# shield.net
KiCad netlist of a schematic drawn in EAGLE
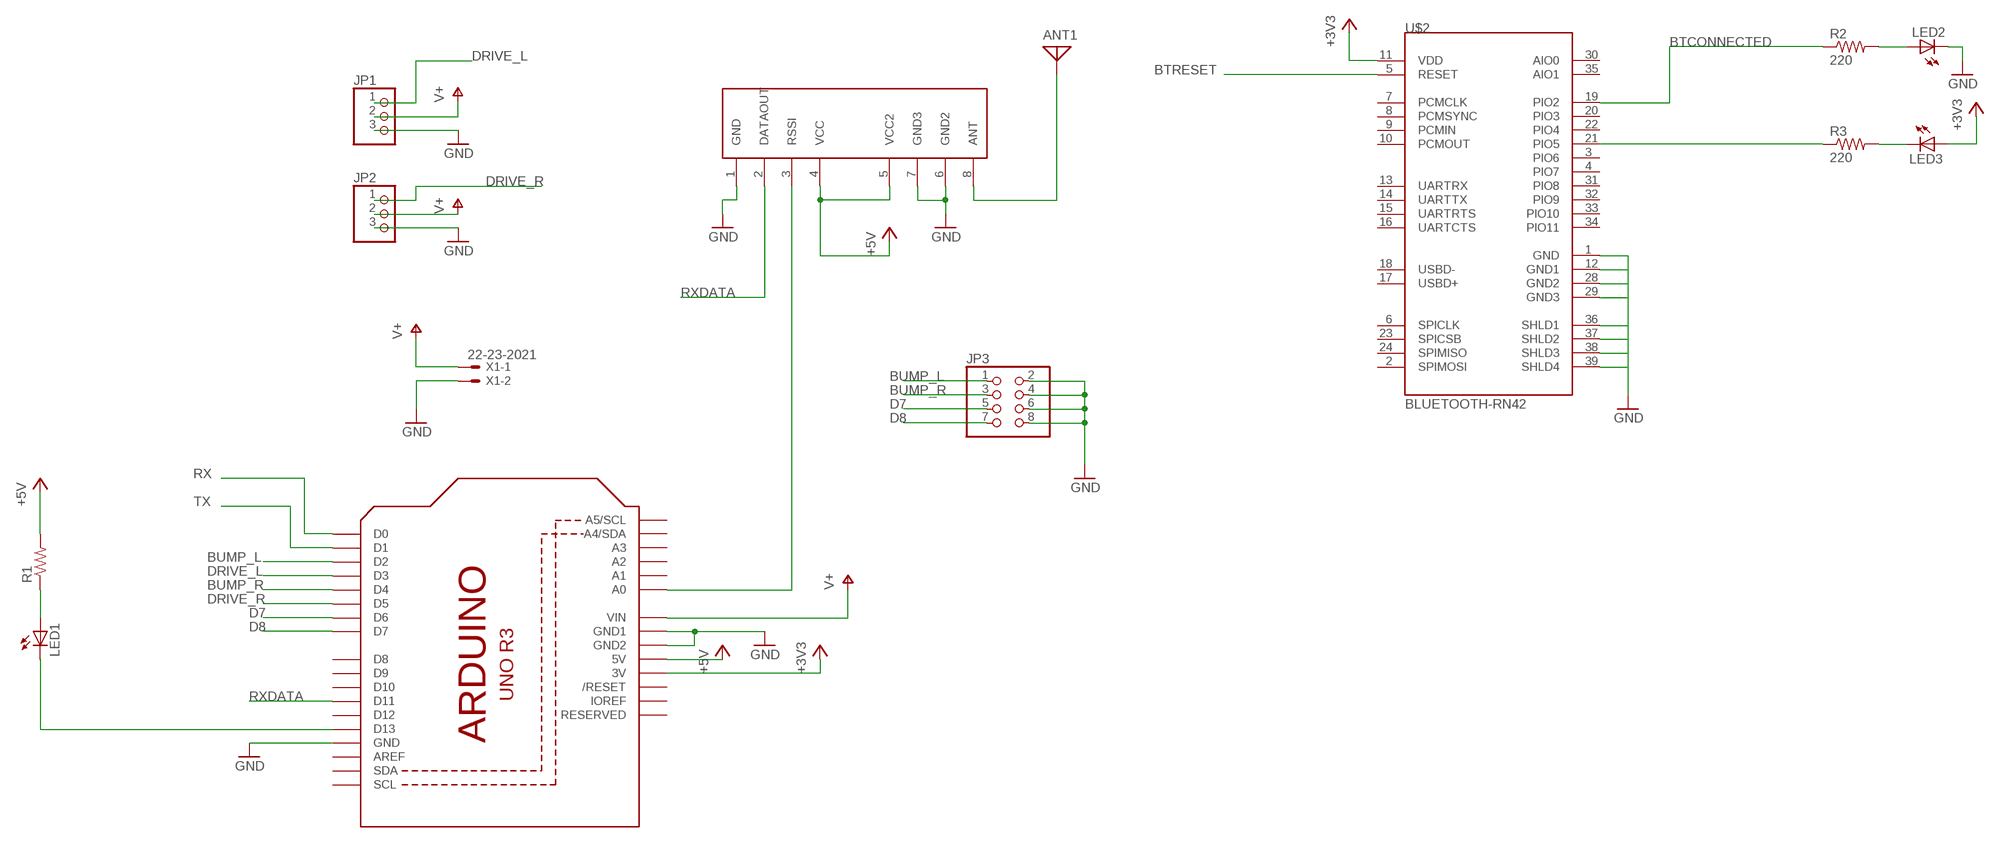
[diagram p0: schematic, sheet 1]

(export (version "E")
  (design (tool "Eeschema 10.0.6"))
  (components
    (comp (ref "ANT1")
      (value "ANTENNA")
      (footprint "eagle-import:PAD-01")
      (libsource (lib "eagle-import") (part "ANTENNA"))
    )
    (comp (ref "JP1")
      (value "PINHD-1X3")
      (footprint "eagle-import:1X03")
      (libsource (lib "eagle-import") (part "PINHD-1X3"))
    )
    (comp (ref "JP2")
      (value "PINHD-1X3")
      (footprint "eagle-import:1X03")
      (libsource (lib "eagle-import") (part "PINHD-1X3"))
    )
    (comp (ref "JP3")
      (value "PINHD-2X4")
      (footprint "eagle-import:2X04")
      (libsource (lib "eagle-import") (part "PINHD-2X4"))
    )
    (comp (ref "LED1")
      (value "LED3MM")
      (footprint "eagle-import:LED3MM")
      (libsource (lib "eagle-import") (part "LED3MM"))
    )
    (comp (ref "LED2")
      (value "LED3MM")
      (footprint "eagle-import:LED3MM")
      (libsource (lib "eagle-import") (part "LED3MM"))
    )
    (comp (ref "LED3")
      (value "LED3MM")
      (footprint "eagle-import:LED3MM")
      (libsource (lib "eagle-import") (part "LED3MM"))
    )
    (comp (ref "R1")
      (value "R-US_R0805")
      (footprint "eagle-import:R0805")
      (libsource (lib "eagle-import") (part "R-US_R0805"))
    )
    (comp (ref "R2")
      (value "220")
      (footprint "eagle-import:R0805")
      (libsource (lib "eagle-import") (part "R-US_R0805"))
    )
    (comp (ref "R3")
      (value "220")
      (footprint "eagle-import:R0805")
      (libsource (lib "eagle-import") (part "R-US_R0805"))
    )
    (comp (ref "U$1")
      (value "RWS371")
      (footprint "eagle-import:RWS-371")
      (libsource (lib "eagle-import") (part "RWS371"))
    )
    (comp (ref "U$2")
      (value "BLUETOOTH-RN42")
      (footprint "eagle-import:RN42")
      (libsource (lib "eagle-import") (part "BLUETOOTH-RN42"))
    )
    (comp (ref "U1")
      (value "ARDUINOR3-DIMENSION")
      (footprint "eagle-import:ARDUINOR3")
      (libsource (lib "eagle-import") (part "ARDUINOR3-DIMENSION"))
    )
    (comp (ref "X1")
      (value "22-23-2021")
      (footprint "eagle-import:22-23-2021")
      (fields (field (name "MF") "MOLEX"))
      (libsource (lib "eagle-import") (part "22-23-2021"))
    )
  )
  (nets
    (net (code "1") (name "+3V3") (class "Default")
      (node (ref "LED3") (pin "A") (pinfunction "A_A") (pintype "passive"))
      (node (ref "U$2") (pin "11") (pinfunction "VDD_11") (pintype "power_in"))
      (node (ref "U1") (pin "3V") (pinfunction "3V_3V") (pintype "power_in"))
    )
    (net (code "2") (name "+5V") (class "Default")
      (node (ref "R1") (pin "2") (pinfunction "2_2") (pintype "passive"))
      (node (ref "U$1") (pin "4") (pinfunction "VCC_4") (pintype "power_in"))
      (node (ref "U$1") (pin "5") (pinfunction "VCC2_5") (pintype "power_in"))
      (node (ref "U1") (pin "5V") (pinfunction "5V_5V") (pintype "power_in"))
    )
    (net (code "3") (name "/BTCONNECTED") (class "Default")
      (node (ref "R2") (pin "1") (pinfunction "1_1") (pintype "passive"))
      (node (ref "U$2") (pin "19") (pinfunction "PIO2_19") (pintype "bidirectional"))
    )
    (net (code "4") (name "/BTRESET") (class "Default")
      (node (ref "U$2") (pin "5") (pinfunction "RESET_5") (pintype "bidirectional"))
    )
    (net (code "5") (name "/BUMP_L") (class "Default")
      (node (ref "JP3") (pin "1") (pinfunction "1_1") (pintype "passive"))
      (node (ref "U1") (pin "D2") (pinfunction "D2_D2") (pintype "bidirectional"))
    )
    (net (code "6") (name "/BUMP_R") (class "Default")
      (node (ref "JP3") (pin "3") (pinfunction "3_3") (pintype "passive"))
      (node (ref "U1") (pin "D4") (pinfunction "D4_D4") (pintype "bidirectional"))
    )
    (net (code "7") (name "/D7") (class "Default")
      (node (ref "JP3") (pin "5") (pinfunction "5_5") (pintype "passive"))
      (node (ref "U1") (pin "D6") (pinfunction "D6_D6") (pintype "bidirectional"))
    )
    (net (code "8") (name "/D8") (class "Default")
      (node (ref "JP3") (pin "7") (pinfunction "7_7") (pintype "passive"))
      (node (ref "U1") (pin "D7") (pinfunction "D7_D7") (pintype "bidirectional"))
    )
    (net (code "9") (name "/DRIVE_L") (class "Default")
      (node (ref "JP1") (pin "1") (pinfunction "1_1") (pintype "passive"))
      (node (ref "U1") (pin "D3") (pinfunction "D3_D3") (pintype "bidirectional"))
    )
    (net (code "10") (name "/DRIVE_R") (class "Default")
      (node (ref "JP2") (pin "1") (pinfunction "1_1") (pintype "passive"))
      (node (ref "U1") (pin "D5") (pinfunction "D5_D5") (pintype "bidirectional"))
    )
    (net (code "11") (name "/RX") (class "Default")
      (node (ref "U1") (pin "D0") (pinfunction "D0_D0") (pintype "bidirectional"))
    )
    (net (code "12") (name "/RXDATA") (class "Default")
      (node (ref "U$1") (pin "2") (pinfunction "DATAOUT_2") (pintype "output"))
      (node (ref "U1") (pin "D11") (pinfunction "D11_D11") (pintype "bidirectional"))
    )
    (net (code "13") (name "/TX") (class "Default")
      (node (ref "U1") (pin "D1") (pinfunction "D1_D1") (pintype "bidirectional"))
    )
    (net (code "14") (name "GND") (class "Default")
      (node (ref "JP1") (pin "3") (pinfunction "3_3") (pintype "passive"))
      (node (ref "JP2") (pin "3") (pinfunction "3_3") (pintype "passive"))
      (node (ref "JP3") (pin "2") (pinfunction "2_2") (pintype "passive"))
      (node (ref "JP3") (pin "4") (pinfunction "4_4") (pintype "passive"))
      (node (ref "JP3") (pin "6") (pinfunction "6_6") (pintype "passive"))
      (node (ref "JP3") (pin "8") (pinfunction "8_8") (pintype "passive"))
      (node (ref "LED2") (pin "K") (pinfunction "C_K") (pintype "passive"))
      (node (ref "U$1") (pin "1") (pinfunction "GND_1") (pintype "power_in"))
      (node (ref "U$1") (pin "6") (pinfunction "GND2_6") (pintype "bidirectional"))
      (node (ref "U$1") (pin "7") (pinfunction "GND3_7") (pintype "bidirectional"))
      (node (ref "U$2") (pin "1") (pinfunction "GND_1") (pintype "power_in"))
      (node (ref "U$2") (pin "12") (pinfunction "GND1_12") (pintype "power_in"))
      (node (ref "U$2") (pin "28") (pinfunction "GND2_28") (pintype "power_in"))
      (node (ref "U$2") (pin "29") (pinfunction "GND3_29") (pintype "power_in"))
      (node (ref "U$2") (pin "36") (pinfunction "SHLD1_36") (pintype "power_in"))
      (node (ref "U$2") (pin "37") (pinfunction "SHLD2_37") (pintype "power_in"))
      (node (ref "U$2") (pin "38") (pinfunction "SHLD3_38") (pintype "power_in"))
      (node (ref "U$2") (pin "39") (pinfunction "SHLD4_39") (pintype "power_in"))
      (node (ref "U1") (pin "GND") (pinfunction "GND_GND") (pintype "power_in"))
      (node (ref "U1") (pin "GND1") (pinfunction "GND1_GND1") (pintype "power_in"))
      (node (ref "U1") (pin "GND2") (pinfunction "GND2_GND2") (pintype "power_in"))
      (node (ref "X1") (pin "2") (pinfunction "S_2") (pintype "passive"))
    )
    (net (code "15") (name "Net-(LED1-C)") (class "Default")
      (node (ref "LED1") (pin "K") (pinfunction "C_K") (pintype "passive"))
      (node (ref "U1") (pin "D13") (pinfunction "D13_D13") (pintype "bidirectional"))
    )
    (net (code "16") (name "Net-(LED1-PadA)") (class "Default")
      (node (ref "LED1") (pin "A") (pinfunction "A_A") (pintype "passive"))
      (node (ref "R1") (pin "1") (pinfunction "1_1") (pintype "passive"))
    )
    (net (code "17") (name "Net-(LED2-PadA)") (class "Default")
      (node (ref "LED2") (pin "A") (pinfunction "A_A") (pintype "passive"))
      (node (ref "R2") (pin "2") (pinfunction "2_2") (pintype "passive"))
    )
    (net (code "18") (name "Net-(LED3-C)") (class "Default")
      (node (ref "LED3") (pin "K") (pinfunction "C_K") (pintype "passive"))
      (node (ref "R3") (pin "2") (pinfunction "2_2") (pintype "passive"))
    )
    (net (code "19") (name "Net-(U$1-ANT)") (class "Default")
      (node (ref "ANT1") (pin "1") (pinfunction "1_1") (pintype "output"))
      (node (ref "U$1") (pin "8") (pinfunction "ANT_8") (pintype "bidirectional"))
    )
    (net (code "20") (name "Net-(U$1-RSSI)") (class "Default")
      (node (ref "U$1") (pin "3") (pinfunction "RSSI_3") (pintype "output"))
      (node (ref "U1") (pin "A0") (pinfunction "A0_A0") (pintype "bidirectional"))
    )
    (net (code "21") (name "Net-(U$2-PIO5)") (class "Default")
      (node (ref "R3") (pin "1") (pinfunction "1_1") (pintype "passive"))
      (node (ref "U$2") (pin "21") (pinfunction "PIO5_21") (pintype "bidirectional"))
    )
    (net (code "22") (name "V+") (class "Default")
      (node (ref "JP1") (pin "2") (pinfunction "2_2") (pintype "passive"))
      (node (ref "JP2") (pin "2") (pinfunction "2_2") (pintype "passive"))
      (node (ref "U1") (pin "VIN") (pinfunction "VIN_VIN") (pintype "power_in"))
      (node (ref "X1") (pin "1") (pinfunction "S_1") (pintype "passive"))
    )
    (net (code "23") (name "unconnected-(U$2-AIO0-Pad30)") (class "Default")
      (node (ref "U$2") (pin "30") (pinfunction "AIO0_30") (pintype "bidirectional"))
    )
    (net (code "24") (name "unconnected-(U$2-AIO1-Pad35)") (class "Default")
      (node (ref "U$2") (pin "35") (pinfunction "AIO1_35") (pintype "bidirectional"))
    )
    (net (code "25") (name "unconnected-(U$2-PCMCLK-Pad7)") (class "Default")
      (node (ref "U$2") (pin "7") (pinfunction "PCMCLK_7") (pintype "bidirectional"))
    )
    (net (code "26") (name "unconnected-(U$2-PCMIN-Pad9)") (class "Default")
      (node (ref "U$2") (pin "9") (pinfunction "PCMIN_9") (pintype "bidirectional"))
    )
    (net (code "27") (name "unconnected-(U$2-PCMOUT-Pad10)") (class "Default")
      (node (ref "U$2") (pin "10") (pinfunction "PCMOUT_10") (pintype "bidirectional"))
    )
    (net (code "28") (name "unconnected-(U$2-PCMSYNC-Pad8)") (class "Default")
      (node (ref "U$2") (pin "8") (pinfunction "PCMSYNC_8") (pintype "bidirectional"))
    )
    (net (code "29") (name "unconnected-(U$2-PIO3-Pad20)") (class "Default")
      (node (ref "U$2") (pin "20") (pinfunction "PIO3_20") (pintype "bidirectional"))
    )
    (net (code "30") (name "unconnected-(U$2-PIO4-Pad22)") (class "Default")
      (node (ref "U$2") (pin "22") (pinfunction "PIO4_22") (pintype "bidirectional"))
    )
    (net (code "31") (name "unconnected-(U$2-PIO6-Pad3)") (class "Default")
      (node (ref "U$2") (pin "3") (pinfunction "PIO6_3") (pintype "bidirectional"))
    )
    (net (code "32") (name "unconnected-(U$2-PIO7-Pad4)") (class "Default")
      (node (ref "U$2") (pin "4") (pinfunction "PIO7_4") (pintype "bidirectional"))
    )
    (net (code "33") (name "unconnected-(U$2-PIO8-Pad31)") (class "Default")
      (node (ref "U$2") (pin "31") (pinfunction "PIO8_31") (pintype "bidirectional"))
    )
    (net (code "34") (name "unconnected-(U$2-PIO9-Pad32)") (class "Default")
      (node (ref "U$2") (pin "32") (pinfunction "PIO9_32") (pintype "bidirectional"))
    )
    (net (code "35") (name "unconnected-(U$2-PIO10-Pad33)") (class "Default")
      (node (ref "U$2") (pin "33") (pinfunction "PIO10_33") (pintype "bidirectional"))
    )
    (net (code "36") (name "unconnected-(U$2-PIO11-Pad34)") (class "Default")
      (node (ref "U$2") (pin "34") (pinfunction "PIO11_34") (pintype "bidirectional"))
    )
    (net (code "37") (name "unconnected-(U$2-SPICLK-Pad6)") (class "Default")
      (node (ref "U$2") (pin "6") (pinfunction "SPICLK_6") (pintype "bidirectional"))
    )
    (net (code "38") (name "unconnected-(U$2-SPICSB-Pad23)") (class "Default")
      (node (ref "U$2") (pin "23") (pinfunction "SPICSB_23") (pintype "bidirectional"))
    )
    (net (code "39") (name "unconnected-(U$2-SPIMISO-Pad24)") (class "Default")
      (node (ref "U$2") (pin "24") (pinfunction "SPIMISO_24") (pintype "bidirectional"))
    )
    (net (code "40") (name "unconnected-(U$2-SPIMOSI-Pad2)") (class "Default")
      (node (ref "U$2") (pin "2") (pinfunction "SPIMOSI_2") (pintype "bidirectional"))
    )
    (net (code "41") (name "unconnected-(U$2-UARTCTS-Pad16)") (class "Default")
      (node (ref "U$2") (pin "16") (pinfunction "UARTCTS_16") (pintype "bidirectional"))
    )
    (net (code "42") (name "unconnected-(U$2-UARTRTS-Pad15)") (class "Default")
      (node (ref "U$2") (pin "15") (pinfunction "UARTRTS_15") (pintype "bidirectional"))
    )
    (net (code "43") (name "unconnected-(U$2-UARTRX-Pad13)") (class "Default")
      (node (ref "U$2") (pin "13") (pinfunction "UARTRX_13") (pintype "bidirectional"))
    )
    (net (code "44") (name "unconnected-(U$2-UARTTX-Pad14)") (class "Default")
      (node (ref "U$2") (pin "14") (pinfunction "UARTTX_14") (pintype "bidirectional"))
    )
    (net (code "45") (name "unconnected-(U$2-USBD+-Pad17)") (class "Default")
      (node (ref "U$2") (pin "17") (pinfunction "USBD+_17") (pintype "bidirectional"))
    )
    (net (code "46") (name "unconnected-(U$2-USBD--Pad18)") (class "Default")
      (node (ref "U$2") (pin "18") (pinfunction "USBD-_18") (pintype "bidirectional"))
    )
    (net (code "47") (name "unconnected-(U1-A4{slash}SDA-PadA4)") (class "Default")
      (node (ref "U1") (pin "A4") (pinfunction "A4/SDA_A4") (pintype "bidirectional"))
    )
    (net (code "48") (name "unconnected-(U1-A5{slash}SCL-PadA5)") (class "Default")
      (node (ref "U1") (pin "A5") (pinfunction "A5/SCL_A5") (pintype "bidirectional"))
    )
    (net (code "49") (name "unconnected-(U1-PadA1)") (class "Default")
      (node (ref "U1") (pin "A1") (pinfunction "A1_A1") (pintype "bidirectional"))
    )
    (net (code "50") (name "unconnected-(U1-PadA2)") (class "Default")
      (node (ref "U1") (pin "A2") (pinfunction "A2_A2") (pintype "bidirectional"))
    )
    (net (code "51") (name "unconnected-(U1-PadA3)") (class "Default")
      (node (ref "U1") (pin "A3") (pinfunction "A3_A3") (pintype "bidirectional"))
    )
    (net (code "52") (name "unconnected-(U1-PadAREF)") (class "Default")
      (node (ref "U1") (pin "AREF") (pinfunction "AREF_AREF") (pintype "bidirectional"))
    )
    (net (code "53") (name "unconnected-(U1-PadD8)") (class "Default")
      (node (ref "U1") (pin "D8") (pinfunction "D8_D8") (pintype "bidirectional"))
    )
    (net (code "54") (name "unconnected-(U1-PadD9)") (class "Default")
      (node (ref "U1") (pin "D9") (pinfunction "D9_D9") (pintype "bidirectional"))
    )
    (net (code "55") (name "unconnected-(U1-PadD10)") (class "Default")
      (node (ref "U1") (pin "D10") (pinfunction "D10_D10") (pintype "bidirectional"))
    )
    (net (code "56") (name "unconnected-(U1-PadD12)") (class "Default")
      (node (ref "U1") (pin "D12") (pinfunction "D12_D12") (pintype "bidirectional"))
    )
    (net (code "57") (name "unconnected-(U1-PadIOREF)") (class "Default")
      (node (ref "U1") (pin "IOREF") (pinfunction "IOREF_IOREF") (pintype "output"))
    )
    (net (code "58") (name "unconnected-(U1-PadRESERVED)") (class "Default")
      (node (ref "U1") (pin "RESERVED") (pinfunction "RESERVED_RESERVED") (pintype "no_connect"))
    )
    (net (code "59") (name "unconnected-(U1-PadSCL)") (class "Default")
      (node (ref "U1") (pin "SCL") (pinfunction "SCL_SCL") (pintype "bidirectional"))
    )
    (net (code "60") (name "unconnected-(U1-PadSDA)") (class "Default")
      (node (ref "U1") (pin "SDA") (pinfunction "SDA_SDA") (pintype "bidirectional"))
    )
    (net (code "61") (name "unconnected-(U1-{slash}RESET-PadRESET)") (class "Default")
      (node (ref "U1") (pin "RESET") (pinfunction "/RESET_RESET") (pintype "bidirectional"))
    )
  )
)
